# Dispenser.net
KiCad netlist of a schematic drawn in Altium Designer
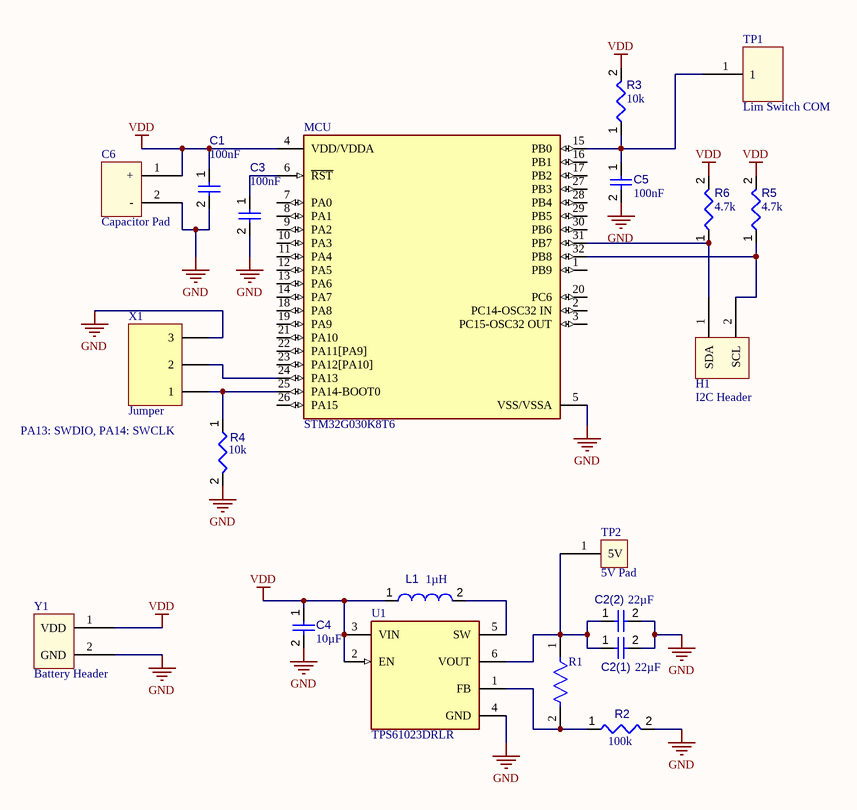
[diagram p0: Dispenser.SchDoc]

(export (version "E")
  (design (tool "Eeschema 10.0.6"))
  (components
    (comp (ref "C1")
      (value "100nF")
      (footprint "CAPC2013X95X50LL10T25")
      (description "Chip Capacitor, 100 nF, +/- 10%, 50 V, 0805 (2012 Metric)")
      (fields (field (name "TOLERANCE") "10%") (field (name "Comment") "Capacitor 100 nF +/-10% 50 V 0805"))
      (libsource (lib "John Moyer") (part "CAP-NP-2"))
    )
    (comp (ref "C2(1)")
      (value "22µF")
      (footprint "CAPC0805(2012)145_L")
      (description "Chip Capacitor, 22µF +/-40%, 16V, 0805, Thickness 1.45 mm")
      (fields (field (name "TOLERANCE") "5%") (field (name "Comment") "Capacitor 22µF +/-40% 16V 0805"))
      (libsource (lib "John Moyer") (part "CAP-NP-2"))
    )
    (comp (ref "C2(2)")
      (value "22µF")
      (footprint "CAPC0805(2012)145_L")
      (description "Chip Capacitor, 22µF +/-40%, 16V, 0805, Thickness 1.45 mm")
      (fields (field (name "TOLERANCE") "5%") (field (name "Comment") "Capacitor 22µF +/-40% 16V 0805"))
      (libsource (lib "John Moyer") (part "CAP-NP-2"))
    )
    (comp (ref "C3")
      (value "100nF")
      (footprint "CAPC1005X56X25LL10T15")
      (description "Chip Capacitor, 0.1 uF, +/- 5%, 16 V, 0402 (1005 Metric)")
      (fields (field (name "TOLERANCE") "5%") (field (name "Comment") "Capacitor 0.1 uF +/- 5% 16 V 0402"))
      (libsource (lib "John Moyer") (part "CAP-NP-2"))
    )
    (comp (ref "C4")
      (value "10µF")
      (footprint "CAPC0603(1608)100_L")
      (description "Chip Capacitor, 10µF +/-20%, 10V, 0603, Thickness 1 mm")
      (fields (field (name "TOLERANCE") "10%") (field (name "Comment") "Capacitor 10µF +/-20% 10V 0603"))
      (libsource (lib "John Moyer") (part "CAP-NP-2"))
    )
    (comp (ref "C5")
      (value "100nF")
      (footprint "CAPC0402(1005)60_L")
      (description "Chip Capacitor, 100nF +/-20%, 10V, 0402, Thickness 0.6 mm")
      (fields (field (name "TOLERANCE") "20%") (field (name "Comment") "Capacitor 100nF +/-20% 10V 0402"))
      (libsource (lib "John Moyer") (part "CAP-NP-2"))
    )
    (comp (ref "C6")
      (value "Capacitor Pad")
      (footprint "CAP_PAD")
      (libsource (lib "Schlib1") (part "CAP_PAD"))
    )
    (comp (ref "H1")
      (value "I2C Header")
      (footprint "HEADER_1X02")
      (libsource (lib "Schlib1") (part "HEADER_1X02"))
    )
    (comp (ref "L1")
      (value "1µH")
      (footprint "INDC2520X120X60NL20T20")
      (description "Chip Inductor, 1 uH, +/- 20%, 1 MHz, -55 to 125 degC, 1008 (2520 Metric), RoHS, Tape and Reel")
      (fields (field (name "TOLERANCE") "20%") (field (name "MANUFACTURER") "Murata"))
      (libsource (lib "John Moyer") (part "IND-2"))
    )
    (comp (ref "MCU")
      (value "STM32G030K8T6")
      (footprint "FP-LQFP32-5V-IPC_A")
      (description "IC MCU 32BIT 64KB FLASH 32LQFP")
      (libsource (lib "Altium Content Vault") (part "fea91388a178aa646681c81fcef9c35"))
    )
    (comp (ref "R1")
      (value "CPF0603B732KE")
      (footprint "FP-CPF0603-MFG")
      (description "RES SMD 732KΩ 0.1% 1/16W 0603")
      (fields (field (name "MANUFACTURER") "TE Connectivity") (field (name "TOLERANCE") "0.1%"))
      (libsource (lib "Altium Content Vault") (part "1029c3af85768c4190bb7ad29bc67b5"))
    )
    (comp (ref "R2")
      (value "100k")
      (footprint "RESC1608X55X25ML10T15")
      (description "Chip Resistor, 100 KOhm, +/- 1%, 0.1 W, -55 to 155 degC, 0603 (1608 Metric)")
      (fields (field (name "TOLERANCE") "1%") (field (name "POWER") "100mW"))
      (libsource (lib "John Moyer") (part "RES-2"))
    )
    (comp (ref "R3")
      (value "10k")
      (footprint "RESC3216X60X45ML15T20")
      (description "Chip Resistor, 10 KOhm, +/- 1%, 0.25 W, -55 to 155 degC, 1206 (3216 Metric)")
      (fields (field (name "TOLERANCE") "1%") (field (name "POWER") "250mW"))
      (libsource (lib "John Moyer") (part "RES-2"))
    )
    (comp (ref "R4")
      (value "10k")
      (footprint "RESC3216X60X45ML15T20")
      (description "Chip Resistor, 10 KOhm, +/- 1%, 0.25 W, -55 to 155 degC, 1206 (3216 Metric)")
      (fields (field (name "TOLERANCE") "1%") (field (name "POWER") "250mW"))
      (libsource (lib "John Moyer") (part "RES-2"))
    )
    (comp (ref "R5")
      (value "4.7k")
      (footprint "RESC3116X70X50ML13T20")
      (description "Chip Resistor, 4.7 KOhm, +/- 1%, 0.25 W, -55 to 155 degC, 1206 (3216 Metric)")
      (fields (field (name "POWER") "250mW") (field (name "TOLERANCE") "1%"))
      (libsource (lib "John Moyer") (part "RES-2"))
    )
    (comp (ref "R6")
      (value "4.7k")
      (footprint "RESC3116X70X50ML13T20")
      (description "Chip Resistor, 4.7 KOhm, +/- 1%, 0.25 W, -55 to 155 degC, 1206 (3216 Metric)")
      (fields (field (name "POWER") "250mW") (field (name "TOLERANCE") "1%"))
      (libsource (lib "John Moyer") (part "RES-2"))
    )
    (comp (ref "TP1")
      (value "Lim Switch COM")
      (footprint "HEADER_1X01")
      (libsource (lib "Schlib1") (part "HEADER_1X01"))
    )
    (comp (ref "TP2") (value "5V Pad") (footprint "PAD_5V") (libsource (lib "Schlib1") (part "PAD_5V")))
    (comp (ref "U1")
      (value "TPS61023DRLR")
      (footprint "FP-DRL0006A-MFG")
      (description "FINISH GOODS FOR TPS61023")
      (libsource (lib "Altium Content Vault") (part "b28b3e956a4ad07201ce69f9d09f9a8"))
    )
    (comp (ref "X1")
      (value "Jumper")
      (footprint "PIN_3_JUMPER")
      (libsource (lib "Schlib1") (part "PIN_3_JUMPER"))
    )
    (comp (ref "Y1")
      (value "Battery Header")
      (footprint "BATTERY_HEADER")
      (libsource (lib "Schlib1") (part "BATTERY_HEADER"))
    )
  )
  (nets
    (net (code "1") (name "GND") (class "Default")
      (node (ref "C1") (pin "2") (pinfunction "2_2") (pintype "passive"))
      (node (ref "C2(1)") (pin "2") (pinfunction "2_2") (pintype "passive"))
      (node (ref "C2(2)") (pin "2") (pinfunction "2_2") (pintype "passive"))
      (node (ref "C3") (pin "2") (pinfunction "2_2") (pintype "passive"))
      (node (ref "C4") (pin "2") (pinfunction "2_2") (pintype "passive"))
      (node (ref "C5") (pin "2") (pinfunction "2_2") (pintype "passive"))
      (node (ref "C6") (pin "2") (pinfunction "-_2") (pintype "passive"))
      (node (ref "MCU") (pin "5") (pinfunction "VSS/VSSA_5") (pintype "power_in"))
      (node (ref "R2") (pin "2") (pinfunction "2_2") (pintype "passive"))
      (node (ref "R4") (pin "2") (pinfunction "2_2") (pintype "passive"))
      (node (ref "U1") (pin "4") (pinfunction "GND_4") (pintype "power_in"))
      (node (ref "X1") (pin "3") (pinfunction "3_3") (pintype "passive"))
      (node (ref "Y1") (pin "2") (pinfunction "GND_2") (pintype "passive"))
    )
    (net (code "2") (name "Net-(H1-SCL)") (class "Default")
      (node (ref "H1") (pin "2") (pinfunction "SCL_2") (pintype "passive"))
      (node (ref "MCU") (pin "32") (pinfunction "PB8_32") (pintype "bidirectional"))
      (node (ref "R5") (pin "1") (pinfunction "1_1") (pintype "passive"))
    )
    (net (code "3") (name "Net-(H1-SDA)") (class "Default")
      (node (ref "H1") (pin "1") (pinfunction "SDA_1") (pintype "passive"))
      (node (ref "MCU") (pin "31") (pinfunction "PB7_31") (pintype "bidirectional"))
      (node (ref "R6") (pin "1") (pinfunction "1_1") (pintype "passive"))
    )
    (net (code "4") (name "Net-(MCU-PA13)") (class "Default")
      (node (ref "MCU") (pin "24") (pinfunction "PA13_24") (pintype "bidirectional"))
      (node (ref "X1") (pin "2") (pinfunction "2_2") (pintype "passive"))
    )
    (net (code "5") (name "Net-(MCU-PA14-BOOT0)") (class "Default")
      (node (ref "MCU") (pin "25") (pinfunction "PA14-BOOT0_25") (pintype "bidirectional"))
      (node (ref "R4") (pin "1") (pinfunction "1_1") (pintype "passive"))
      (node (ref "X1") (pin "1") (pinfunction "1_1") (pintype "passive"))
    )
    (net (code "6") (name "Net-(MCU-PB0)") (class "Default")
      (node (ref "C5") (pin "1") (pinfunction "1_1") (pintype "passive"))
      (node (ref "MCU") (pin "15") (pinfunction "PB0_15") (pintype "bidirectional"))
      (node (ref "R3") (pin "1") (pinfunction "1_1") (pintype "passive"))
      (node (ref "TP1") (pin "1") (pinfunction "1_1") (pintype "passive"))
    )
    (net (code "7") (name "Net-(MCU-~{RST})") (class "Default")
      (node (ref "C3") (pin "1") (pinfunction "1_1") (pintype "passive"))
      (node (ref "MCU") (pin "6") (pinfunction "~{RST}_6") (pintype "input"))
    )
    (net (code "8") (name "Net-(TP2-5V)") (class "Default")
      (node (ref "C2(1)") (pin "1") (pinfunction "1_1") (pintype "passive"))
      (node (ref "C2(2)") (pin "1") (pinfunction "1_1") (pintype "passive"))
      (node (ref "R1") (pin "1") (pinfunction "1_1") (pintype "passive"))
      (node (ref "TP2") (pin "1") (pinfunction "5V_1") (pintype "passive"))
      (node (ref "U1") (pin "6") (pinfunction "VOUT_6") (pintype "power_in"))
    )
    (net (code "9") (name "Net-(U1-FB)") (class "Default")
      (node (ref "R1") (pin "2") (pinfunction "2_2") (pintype "passive"))
      (node (ref "R2") (pin "1") (pinfunction "1_1") (pintype "passive"))
      (node (ref "U1") (pin "1") (pinfunction "FB_1") (pintype "passive"))
    )
    (net (code "10") (name "Net-(U1-SW)") (class "Default")
      (node (ref "L1") (pin "2") (pinfunction "2_2") (pintype "passive"))
      (node (ref "U1") (pin "5") (pinfunction "SW_5") (pintype "passive"))
    )
    (net (code "11") (name "VDD") (class "Default")
      (node (ref "C1") (pin "1") (pinfunction "1_1") (pintype "passive"))
      (node (ref "C4") (pin "1") (pinfunction "1_1") (pintype "passive"))
      (node (ref "C6") (pin "1") (pinfunction "+_1") (pintype "passive"))
      (node (ref "L1") (pin "1") (pinfunction "1_1") (pintype "passive"))
      (node (ref "MCU") (pin "4") (pinfunction "VDD/VDDA_4") (pintype "power_in"))
      (node (ref "R3") (pin "2") (pinfunction "2_2") (pintype "passive"))
      (node (ref "R5") (pin "2") (pinfunction "2_2") (pintype "passive"))
      (node (ref "R6") (pin "2") (pinfunction "2_2") (pintype "passive"))
      (node (ref "U1") (pin "2") (pinfunction "EN_2") (pintype "input"))
      (node (ref "U1") (pin "3") (pinfunction "VIN_3") (pintype "power_in"))
      (node (ref "Y1") (pin "1") (pinfunction "VDD_1") (pintype "passive"))
    )
    (net (code "12") (name "unconnected-(MCU-PA0-Pad7)") (class "Default")
      (node (ref "MCU") (pin "7") (pinfunction "PA0_7") (pintype "bidirectional"))
    )
    (net (code "13") (name "unconnected-(MCU-PA1-Pad8)") (class "Default")
      (node (ref "MCU") (pin "8") (pinfunction "PA1_8") (pintype "bidirectional"))
    )
    (net (code "14") (name "unconnected-(MCU-PA2-Pad9)") (class "Default")
      (node (ref "MCU") (pin "9") (pinfunction "PA2_9") (pintype "bidirectional"))
    )
    (net (code "15") (name "unconnected-(MCU-PA3-Pad10)") (class "Default")
      (node (ref "MCU") (pin "10") (pinfunction "PA3_10") (pintype "bidirectional"))
    )
    (net (code "16") (name "unconnected-(MCU-PA4-Pad11)") (class "Default")
      (node (ref "MCU") (pin "11") (pinfunction "PA4_11") (pintype "bidirectional"))
    )
    (net (code "17") (name "unconnected-(MCU-PA5-Pad12)") (class "Default")
      (node (ref "MCU") (pin "12") (pinfunction "PA5_12") (pintype "bidirectional"))
    )
    (net (code "18") (name "unconnected-(MCU-PA6-Pad13)") (class "Default")
      (node (ref "MCU") (pin "13") (pinfunction "PA6_13") (pintype "bidirectional"))
    )
    (net (code "19") (name "unconnected-(MCU-PA7-Pad14)") (class "Default")
      (node (ref "MCU") (pin "14") (pinfunction "PA7_14") (pintype "bidirectional"))
    )
    (net (code "20") (name "unconnected-(MCU-PA8-Pad18)") (class "Default")
      (node (ref "MCU") (pin "18") (pinfunction "PA8_18") (pintype "bidirectional"))
    )
    (net (code "21") (name "unconnected-(MCU-PA9-Pad19)") (class "Default")
      (node (ref "MCU") (pin "19") (pinfunction "PA9_19") (pintype "bidirectional"))
    )
    (net (code "22") (name "unconnected-(MCU-PA10-Pad21)") (class "Default")
      (node (ref "MCU") (pin "21") (pinfunction "PA10_21") (pintype "bidirectional"))
    )
    (net (code "23") (name "unconnected-(MCU-PA11[PA9]-Pad22)") (class "Default")
      (node (ref "MCU") (pin "22") (pinfunction "PA11[PA9]_22") (pintype "bidirectional"))
    )
    (net (code "24") (name "unconnected-(MCU-PA12[PA10]-Pad23)") (class "Default")
      (node (ref "MCU") (pin "23") (pinfunction "PA12[PA10]_23") (pintype "bidirectional"))
    )
    (net (code "25") (name "unconnected-(MCU-PA15-Pad26)") (class "Default")
      (node (ref "MCU") (pin "26") (pinfunction "PA15_26") (pintype "bidirectional"))
    )
    (net (code "26") (name "unconnected-(MCU-PB1-Pad16)") (class "Default")
      (node (ref "MCU") (pin "16") (pinfunction "PB1_16") (pintype "bidirectional"))
    )
    (net (code "27") (name "unconnected-(MCU-PB2-Pad17)") (class "Default")
      (node (ref "MCU") (pin "17") (pinfunction "PB2_17") (pintype "bidirectional"))
    )
    (net (code "28") (name "unconnected-(MCU-PB3-Pad27)") (class "Default")
      (node (ref "MCU") (pin "27") (pinfunction "PB3_27") (pintype "bidirectional"))
    )
    (net (code "29") (name "unconnected-(MCU-PB4-Pad28)") (class "Default")
      (node (ref "MCU") (pin "28") (pinfunction "PB4_28") (pintype "bidirectional"))
    )
    (net (code "30") (name "unconnected-(MCU-PB5-Pad29)") (class "Default")
      (node (ref "MCU") (pin "29") (pinfunction "PB5_29") (pintype "bidirectional"))
    )
    (net (code "31") (name "unconnected-(MCU-PB6-Pad30)") (class "Default")
      (node (ref "MCU") (pin "30") (pinfunction "PB6_30") (pintype "bidirectional"))
    )
    (net (code "32") (name "unconnected-(MCU-PB9-Pad1)") (class "Default")
      (node (ref "MCU") (pin "1") (pinfunction "PB9_1") (pintype "bidirectional"))
    )
    (net (code "33") (name "unconnected-(MCU-PC6-Pad20)") (class "Default")
      (node (ref "MCU") (pin "20") (pinfunction "PC6_20") (pintype "bidirectional"))
    )
    (net (code "34") (name "unconnected-(MCU-PC14-OSC32_IN-Pad2)") (class "Default")
      (node (ref "MCU") (pin "2") (pinfunction "PC14-OSC32_IN_2") (pintype "bidirectional"))
    )
    (net (code "35") (name "unconnected-(MCU-PC15-OSC32_OUT-Pad3)") (class "Default")
      (node (ref "MCU") (pin "3") (pinfunction "PC15-OSC32_OUT_3") (pintype "bidirectional"))
    )
  )
)
